# FTDI_Basic-5V.net
KiCad netlist of a schematic drawn in EAGLE
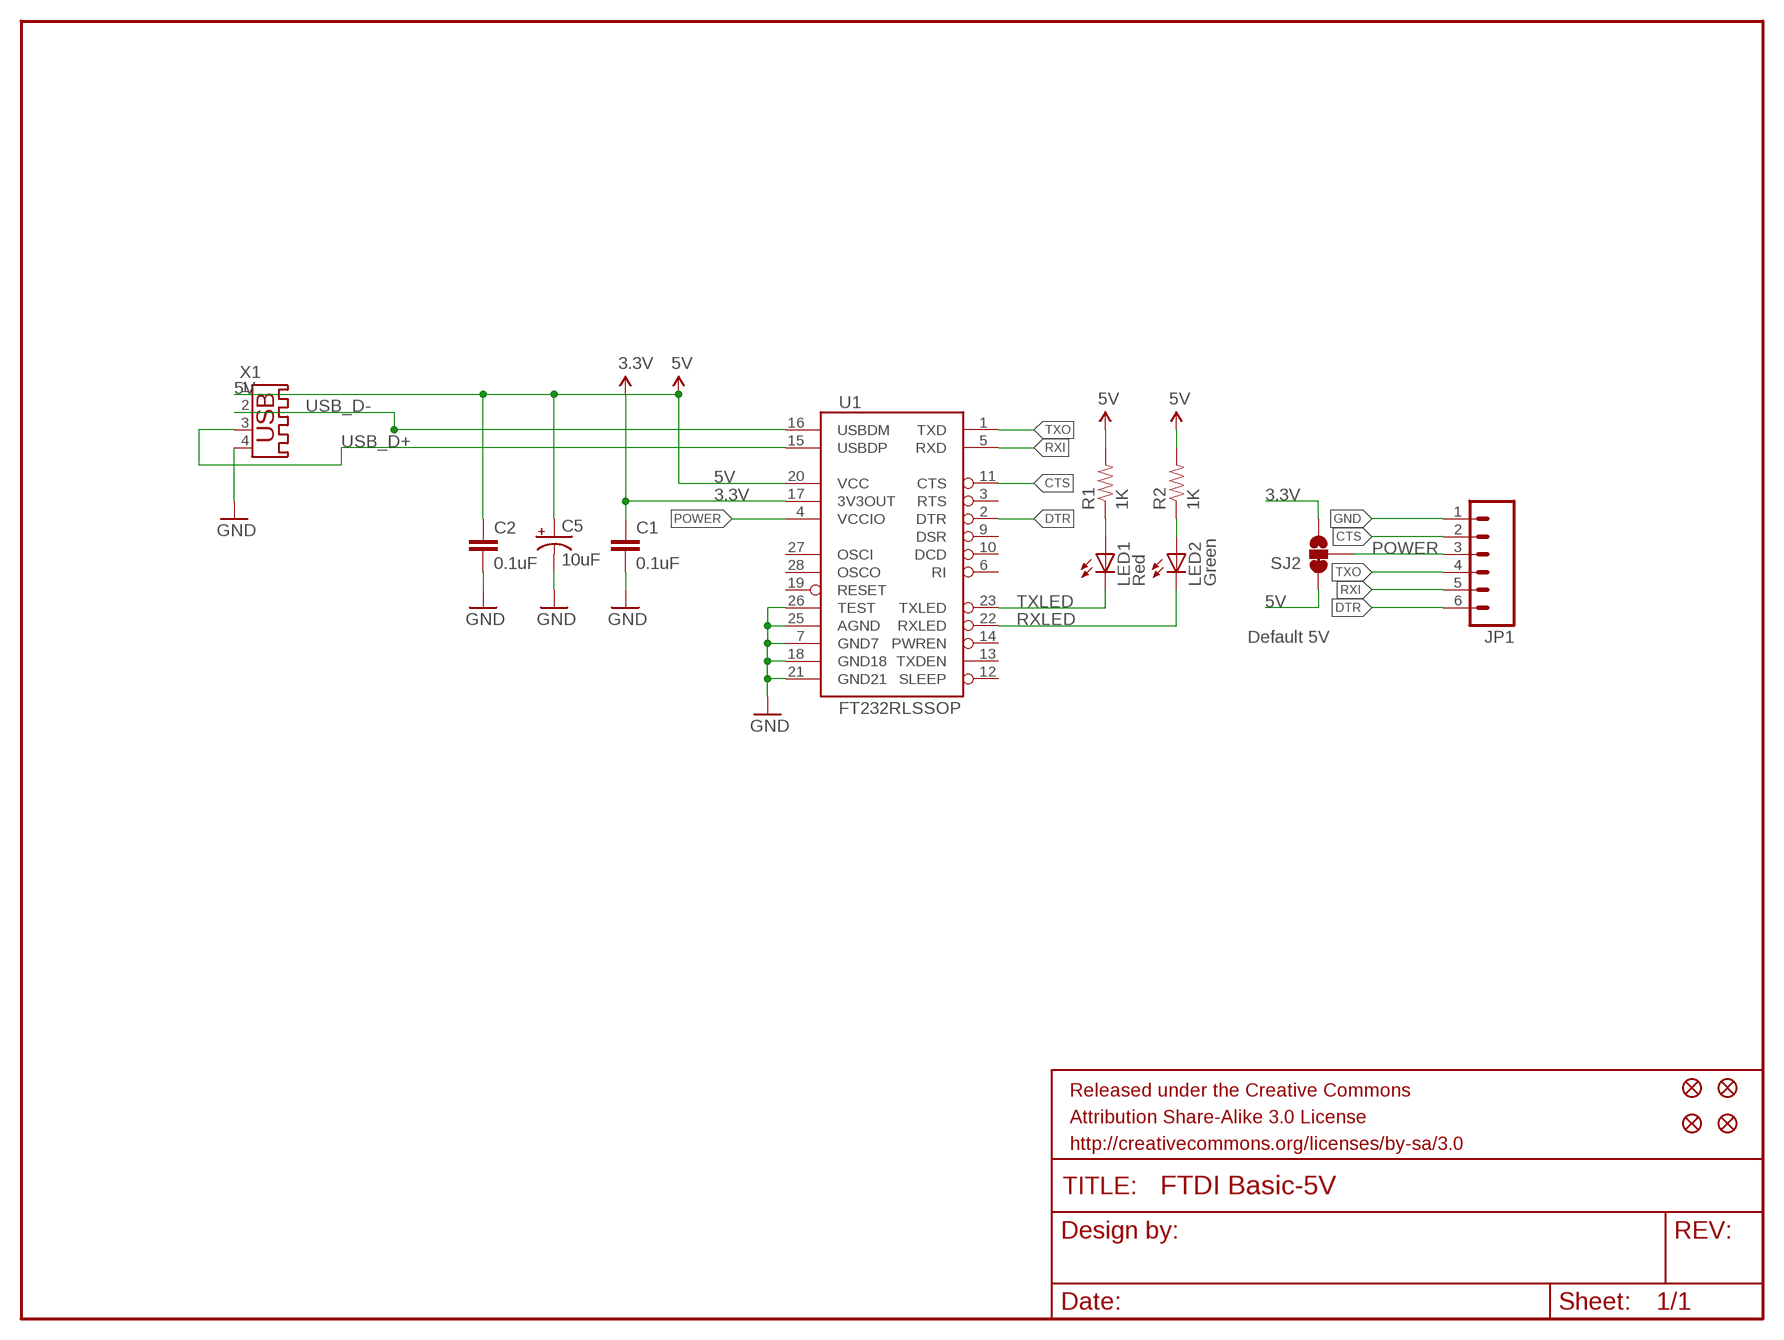
[diagram p0: schematic, sheet 1]

(export (version "E")
  (design (tool "Eeschema 10.0.6"))
  (components
    (comp (ref "C1")
      (value "0.1uF")
      (footprint "eagle-import:0603-CAP")
      (libsource (lib "eagle-import") (part "CAP0603-CAP"))
    )
    (comp (ref "C2")
      (value "0.1uF")
      (footprint "eagle-import:0603-CAP")
      (libsource (lib "eagle-import") (part "CAP0603-CAP"))
    )
    (comp (ref "C5")
      (value "10uF")
      (footprint "eagle-import:EIA3216")
      (libsource (lib "eagle-import") (part "CAP_POL1206"))
    )
    (comp (ref "FRAME1")
      (value "FRAME-LETTER")
      (footprint "eagle-import:CREATIVE_COMMONS")
      (libsource (lib "eagle-import") (part "FRAME-LETTER"))
    )
    (comp (ref "JP1")
      (value "M06SMD-FEMALE-V2")
      (footprint "eagle-import:1X06-SMD-FEMALE-V2")
      (libsource (lib "eagle-import") (part "M06SMD-FEMALE-V2"))
    )
    (comp (ref "JP3")
      (value "FIDUCIAL1X2")
      (footprint "eagle-import:FIDUCIAL-1X2")
      (libsource (lib "eagle-import") (part "FIDUCIAL1X2"))
    )
    (comp (ref "JP4")
      (value "FIDUCIAL1X2")
      (footprint "eagle-import:FIDUCIAL-1X2")
      (libsource (lib "eagle-import") (part "FIDUCIAL1X2"))
    )
    (comp (ref "JP5")
      (value "FIDUCIAL1X2")
      (footprint "eagle-import:FIDUCIAL-1X2")
      (libsource (lib "eagle-import") (part "FIDUCIAL1X2"))
    )
    (comp (ref "JP6")
      (value "FIDUCIAL1X2")
      (footprint "eagle-import:FIDUCIAL-1X2")
      (libsource (lib "eagle-import") (part "FIDUCIAL1X2"))
    )
    (comp (ref "LED1")
      (value "Red")
      (footprint "eagle-import:LED-0603")
      (libsource (lib "eagle-import") (part "LED0603"))
    )
    (comp (ref "LED2")
      (value "Green")
      (footprint "eagle-import:LED-0603")
      (libsource (lib "eagle-import") (part "LED0603"))
    )
    (comp (ref "R1")
      (value "1K")
      (footprint "eagle-import:0603-RES")
      (libsource (lib "eagle-import") (part "RESISTOR0603-RES"))
    )
    (comp (ref "R2")
      (value "1K")
      (footprint "eagle-import:0603-RES")
      (libsource (lib "eagle-import") (part "RESISTOR0603-RES"))
    )
    (comp (ref "SJ2")
      (value "SOLDERJUMPER_2WAYS")
      (footprint "eagle-import:SJ_3")
      (libsource (lib "eagle-import") (part "SOLDERJUMPER_2WAYS"))
    )
    (comp (ref "U1")
      (value "FT232RLSSOP")
      (footprint "eagle-import:SSOP28DB")
      (libsource (lib "eagle-import") (part "FT232RLSSOP"))
    )
    (comp (ref "X1")
      (value "USB-A003")
      (footprint "eagle-import:USB-A003")
      (libsource (lib "eagle-import") (part "USB-A003"))
    )
  )
  (nets
    (net (code "1") (name "/RXLED") (class "Default")
      (node (ref "LED2") (pin "C") (pinfunction "C_C") (pintype "passive"))
      (node (ref "U1") (pin "22") (pinfunction "RXLED_22") (pintype "input"))
    )
    (net (code "2") (name "/TXLED") (class "Default")
      (node (ref "LED1") (pin "C") (pinfunction "C_C") (pintype "passive"))
      (node (ref "U1") (pin "23") (pinfunction "TXLED_23") (pintype "input"))
    )
    (net (code "3") (name "/USB_D+") (class "Default")
      (node (ref "U1") (pin "15") (pinfunction "USBDP_15") (pintype "bidirectional"))
      (node (ref "X1") (pin "3") (pinfunction "3_3") (pintype "passive"))
    )
    (net (code "4") (name "/USB_D-") (class "Default")
      (node (ref "U1") (pin "16") (pinfunction "USBDM_16") (pintype "bidirectional"))
      (node (ref "X1") (pin "2") (pinfunction "2_2") (pintype "passive"))
    )
    (net (code "5") (name "3.3V") (class "Default")
      (node (ref "C1") (pin "1") (pinfunction "1_1") (pintype "passive"))
      (node (ref "SJ2") (pin "3") (pinfunction "3_3") (pintype "passive"))
      (node (ref "U1") (pin "17") (pinfunction "3V3OUT_17") (pintype "output"))
    )
    (net (code "6") (name "5V") (class "Default")
      (node (ref "C2") (pin "1") (pinfunction "1_1") (pintype "passive"))
      (node (ref "C5") (pin "A") (pinfunction "+_A") (pintype "passive"))
      (node (ref "R1") (pin "2") (pinfunction "2_2") (pintype "passive"))
      (node (ref "R2") (pin "2") (pinfunction "2_2") (pintype "passive"))
      (node (ref "SJ2") (pin "1") (pinfunction "1_1") (pintype "passive"))
      (node (ref "U1") (pin "20") (pinfunction "VCC_20") (pintype "power_in"))
      (node (ref "X1") (pin "1") (pinfunction "1_1") (pintype "passive"))
    )
    (net (code "7") (name "CTS") (class "Default")
      (node (ref "JP1") (pin "2") (pinfunction "2_2") (pintype "passive"))
      (node (ref "U1") (pin "11") (pinfunction "CTS_11") (pintype "input"))
    )
    (net (code "8") (name "DTR") (class "Default")
      (node (ref "JP1") (pin "6") (pinfunction "6_6") (pintype "passive"))
      (node (ref "U1") (pin "2") (pinfunction "DTR_2") (pintype "output"))
    )
    (net (code "9") (name "GND") (class "Default")
      (node (ref "C1") (pin "2") (pinfunction "2_2") (pintype "passive"))
      (node (ref "C2") (pin "2") (pinfunction "2_2") (pintype "passive"))
      (node (ref "C5") (pin "C") (pinfunction "-_C") (pintype "passive"))
      (node (ref "JP1") (pin "1") (pinfunction "1_1") (pintype "passive"))
      (node (ref "U1") (pin "18") (pinfunction "GND18_18") (pintype "power_in"))
      (node (ref "U1") (pin "21") (pinfunction "GND21_21") (pintype "power_in"))
      (node (ref "U1") (pin "25") (pinfunction "AGND_25") (pintype "power_in"))
      (node (ref "U1") (pin "26") (pinfunction "TEST_26") (pintype "input"))
      (node (ref "U1") (pin "7") (pinfunction "GND7_7") (pintype "power_in"))
      (node (ref "X1") (pin "4") (pinfunction "4_4") (pintype "passive"))
    )
    (net (code "10") (name "Net-(LED1-PadA)") (class "Default")
      (node (ref "LED1") (pin "A") (pinfunction "A_A") (pintype "passive"))
      (node (ref "R1") (pin "1") (pinfunction "1_1") (pintype "passive"))
    )
    (net (code "11") (name "Net-(LED2-PadA)") (class "Default")
      (node (ref "LED2") (pin "A") (pinfunction "A_A") (pintype "passive"))
      (node (ref "R2") (pin "1") (pinfunction "1_1") (pintype "passive"))
    )
    (net (code "12") (name "POWER") (class "Default")
      (node (ref "JP1") (pin "3") (pinfunction "3_3") (pintype "passive"))
      (node (ref "SJ2") (pin "2") (pinfunction "2_2") (pintype "passive"))
      (node (ref "U1") (pin "4") (pinfunction "VCCIO_4") (pintype "power_in"))
    )
    (net (code "13") (name "RXI") (class "Default")
      (node (ref "JP1") (pin "5") (pinfunction "5_5") (pintype "passive"))
      (node (ref "U1") (pin "5") (pinfunction "RXD_5") (pintype "input"))
    )
    (net (code "14") (name "TXO") (class "Default")
      (node (ref "JP1") (pin "4") (pinfunction "4_4") (pintype "passive"))
      (node (ref "U1") (pin "1") (pinfunction "TXD_1") (pintype "output"))
    )
    (net (code "15") (name "unconnected-(U1-DCD-Pad10)") (class "Default")
      (node (ref "U1") (pin "10") (pinfunction "DCD_10") (pintype "input"))
    )
    (net (code "16") (name "unconnected-(U1-DSR-Pad9)") (class "Default")
      (node (ref "U1") (pin "9") (pinfunction "DSR_9") (pintype "input"))
    )
    (net (code "17") (name "unconnected-(U1-OSCI-Pad27)") (class "Default")
      (node (ref "U1") (pin "27") (pinfunction "OSCI_27") (pintype "input"))
    )
    (net (code "18") (name "unconnected-(U1-OSCO-Pad28)") (class "Default")
      (node (ref "U1") (pin "28") (pinfunction "OSCO_28") (pintype "output"))
    )
    (net (code "19") (name "unconnected-(U1-PWREN-Pad14)") (class "Default")
      (node (ref "U1") (pin "14") (pinfunction "PWREN_14") (pintype "input"))
    )
    (net (code "20") (name "unconnected-(U1-RESET-Pad19)") (class "Default")
      (node (ref "U1") (pin "19") (pinfunction "RESET_19") (pintype "input"))
    )
    (net (code "21") (name "unconnected-(U1-RI-Pad6)") (class "Default")
      (node (ref "U1") (pin "6") (pinfunction "RI_6") (pintype "input"))
    )
    (net (code "22") (name "unconnected-(U1-RTS-Pad3)") (class "Default")
      (node (ref "U1") (pin "3") (pinfunction "RTS_3") (pintype "output"))
    )
    (net (code "23") (name "unconnected-(U1-SLEEP-Pad12)") (class "Default")
      (node (ref "U1") (pin "12") (pinfunction "SLEEP_12") (pintype "input"))
    )
    (net (code "24") (name "unconnected-(U1-TXDEN-Pad13)") (class "Default")
      (node (ref "U1") (pin "13") (pinfunction "TXDEN_13") (pintype "input"))
    )
  )
)
